# jtag-adapter-3-3.net
KiCad netlist of a schematic drawn in EAGLE
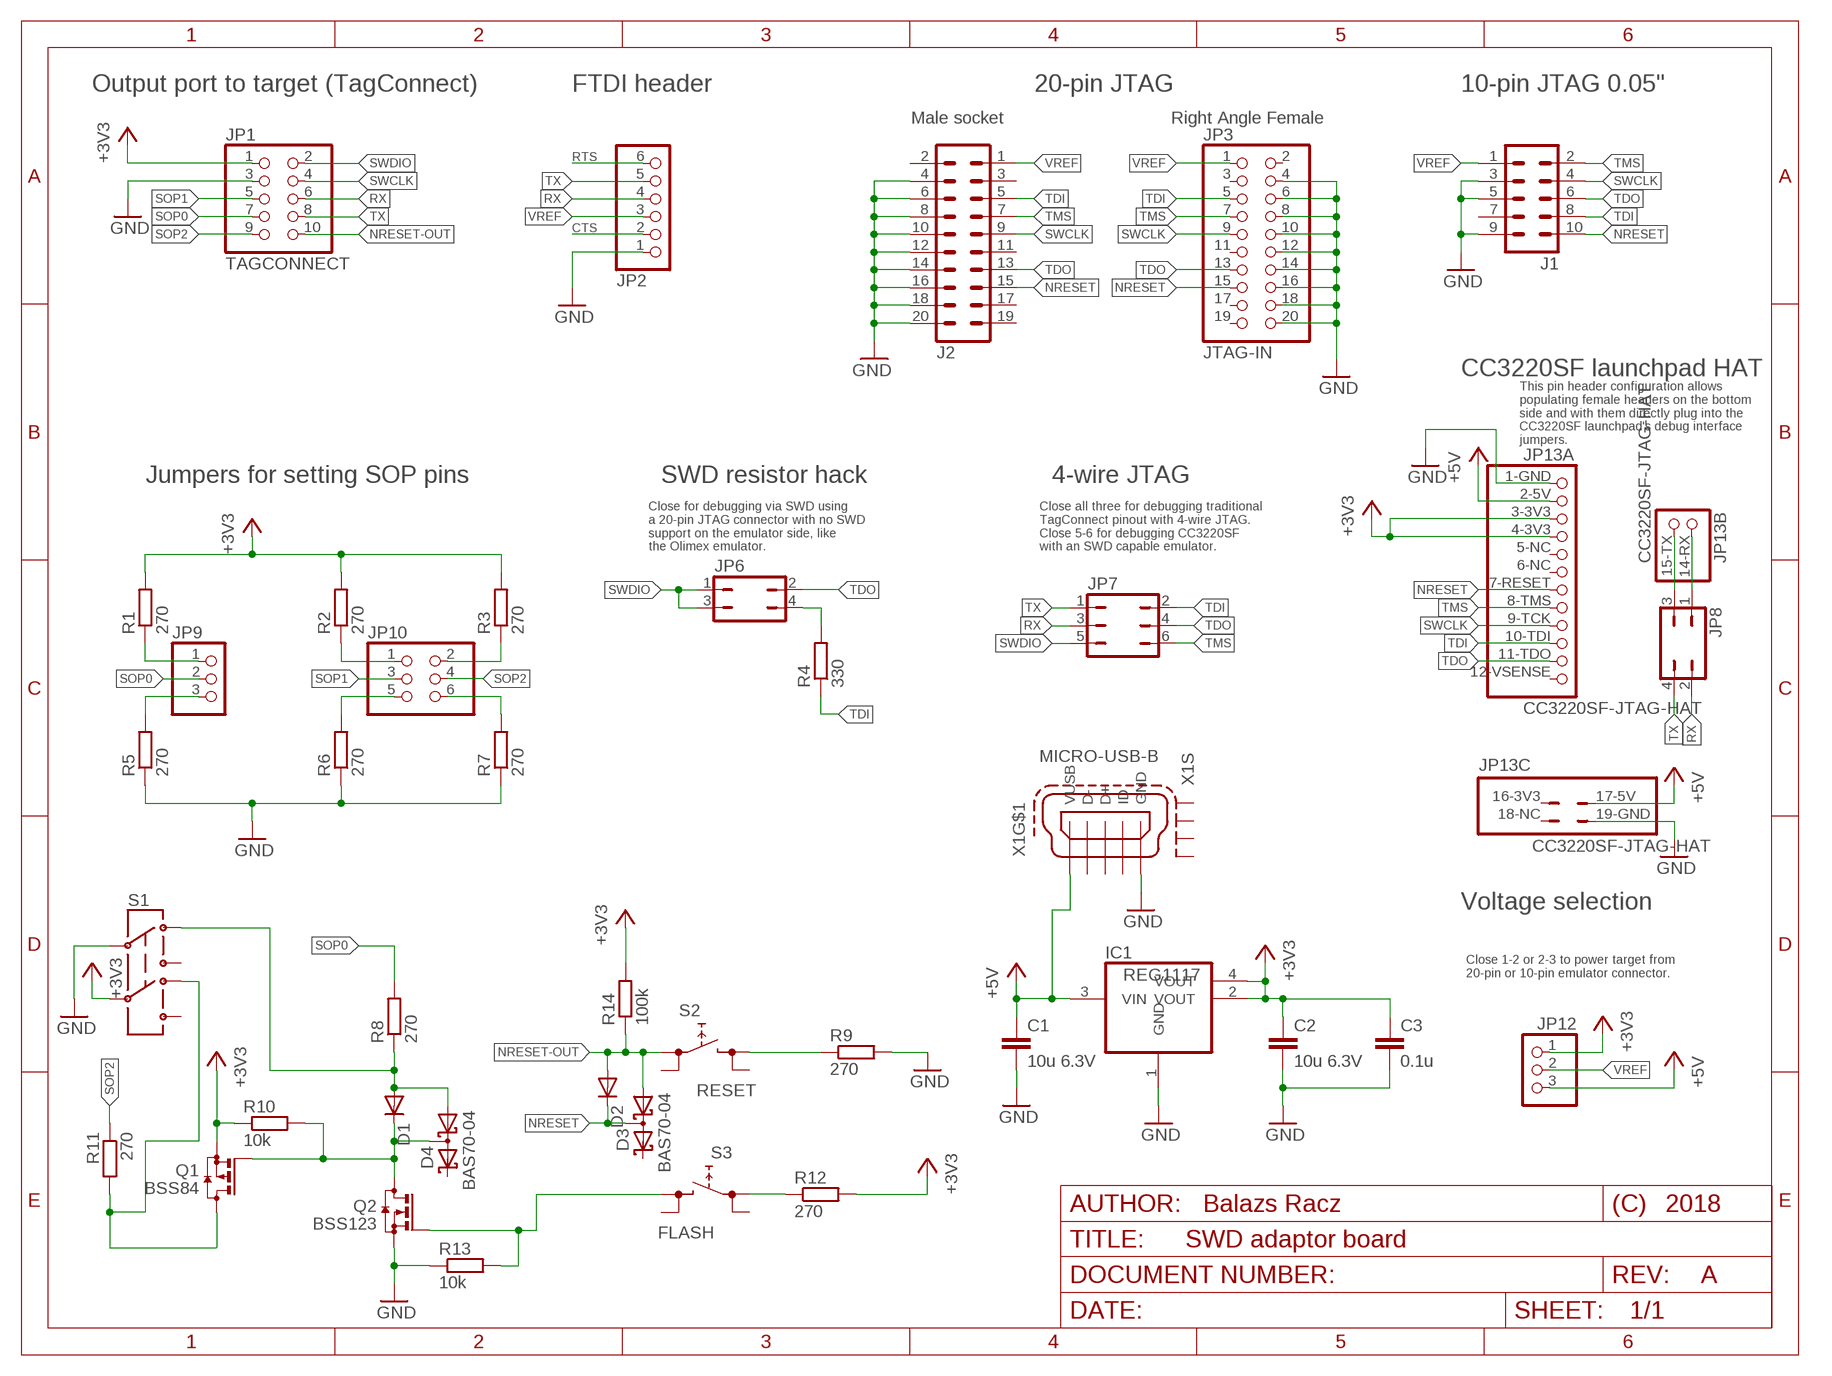
[diagram p0: schematic, sheet 1]

(export (version "E")
  (design (tool "Eeschema 10.0.6"))
  (components
    (comp (ref "C1")
      (value "10u 6.3V")
      (footprint "eagle-import:C0603K")
      (libsource (lib "eagle-import") (part "C-EUC0603K"))
    )
    (comp (ref "C2")
      (value "10u 6.3V")
      (footprint "eagle-import:C0603K")
      (libsource (lib "eagle-import") (part "C-EUC0603K"))
    )
    (comp (ref "C3")
      (value "0.1u")
      (footprint "eagle-import:C0603K")
      (libsource (lib "eagle-import") (part "C-EUC0603K"))
    )
    (comp (ref "D1")
      (value "DIODE-MINIMELF")
      (footprint "eagle-import:MINIMELF")
      (libsource (lib "eagle-import") (part "DIODE-MINIMELF"))
    )
    (comp (ref "D2")
      (value "DIODE-MINIMELF")
      (footprint "eagle-import:MINIMELF")
      (libsource (lib "eagle-import") (part "DIODE-MINIMELF"))
    )
    (comp (ref "D3")
      (value "BAS70-04")
      (footprint "eagle-import:SOT23")
      (libsource (lib "eagle-import") (part "BAS70-04"))
    )
    (comp (ref "D4")
      (value "BAS70-04")
      (footprint "eagle-import:SOT23")
      (libsource (lib "eagle-import") (part "BAS70-04"))
    )
    (comp (ref "IC1")
      (value "REG1117")
      (footprint "eagle-import:SOT223")
      (libsource (lib "eagle-import") (part "REG1117"))
    )
    (comp (ref "J1")
      (value "MA05-2_0.05X0.05")
      (footprint "eagle-import:MA05-2_0.05_X_0.05")
      (libsource (lib "eagle-import") (part "MA05-2_0.05X0.05"))
    )
    (comp (ref "J2")
      (value "MA10-2S")
      (footprint "eagle-import:MA10-2-SHROUDED")
      (libsource (lib "eagle-import") (part "MA10-2S"))
    )
    (comp (ref "JP1")
      (value "TAGCONNECT")
      (footprint "eagle-import:CON10M")
      (libsource (lib "eagle-import") (part "PINHD-2X5CN"))
    )
    (comp (ref "JP2")
      (value "PINHD-1X6")
      (footprint "eagle-import:1X06")
      (libsource (lib "eagle-import") (part "PINHD-1X6"))
    )
    (comp (ref "JP3")
      (value "JTAG-IN")
      (footprint "eagle-import:2X10")
      (libsource (lib "eagle-import") (part "PINHD-2X10"))
    )
    (comp (ref "JP6")
      (value "JP2Q")
      (footprint "eagle-import:JP2Q")
      (libsource (lib "eagle-import") (part "JP2Q"))
    )
    (comp (ref "JP7")
      (value "JP3Q")
      (footprint "eagle-import:JP3Q")
      (libsource (lib "eagle-import") (part "JP3Q"))
    )
    (comp (ref "JP8")
      (value "JP2Q")
      (footprint "eagle-import:JP2Q")
      (libsource (lib "eagle-import") (part "JP2Q"))
    )
    (comp (ref "JP9")
      (value "PINHD-1X3")
      (footprint "eagle-import:1X03")
      (libsource (lib "eagle-import") (part "PINHD-1X3"))
    )
    (comp (ref "JP10")
      (value "PINHD-2X3")
      (footprint "eagle-import:2X03")
      (libsource (lib "eagle-import") (part "PINHD-2X3"))
    )
    (comp (ref "JP12")
      (value "PINHD-1X3")
      (footprint "eagle-import:1X03")
      (libsource (lib "eagle-import") (part "PINHD-1X3"))
    )
    (comp (ref "JP13")
      (value "CC3220SF-JTAG-HAT")
      (footprint "eagle-import:JTAG-LAUNCHPAD-3220SF")
      (libsource (lib "eagle-import") (part "CC3220SF-JTAG-HAT"))
    )
    (comp (ref "Q1")
      (value "BSS84")
      (footprint "eagle-import:SOT23")
      (libsource (lib "eagle-import") (part "BSS84"))
    )
    (comp (ref "Q2")
      (value "BSS123")
      (footprint "eagle-import:SOT23")
      (libsource (lib "eagle-import") (part "BSS123"))
    )
    (comp (ref "R1")
      (value "270")
      (footprint "eagle-import:R0805")
      (libsource (lib "eagle-import") (part "R-EU_R0805"))
    )
    (comp (ref "R2")
      (value "270")
      (footprint "eagle-import:R0805")
      (libsource (lib "eagle-import") (part "R-EU_R0805"))
    )
    (comp (ref "R3")
      (value "270")
      (footprint "eagle-import:R0805")
      (libsource (lib "eagle-import") (part "R-EU_R0805"))
    )
    (comp (ref "R4")
      (value "330")
      (footprint "eagle-import:R0805")
      (libsource (lib "eagle-import") (part "R-EU_R0805"))
    )
    (comp (ref "R5")
      (value "270")
      (footprint "eagle-import:R0805")
      (libsource (lib "eagle-import") (part "R-EU_R0805"))
    )
    (comp (ref "R6")
      (value "270")
      (footprint "eagle-import:R0805")
      (libsource (lib "eagle-import") (part "R-EU_R0805"))
    )
    (comp (ref "R7")
      (value "270")
      (footprint "eagle-import:R0805")
      (libsource (lib "eagle-import") (part "R-EU_R0805"))
    )
    (comp (ref "R8")
      (value "270")
      (footprint "eagle-import:R0805")
      (libsource (lib "eagle-import") (part "R-EU_R0805"))
    )
    (comp (ref "R9")
      (value "270")
      (footprint "eagle-import:R0805")
      (libsource (lib "eagle-import") (part "R-EU_R0805"))
    )
    (comp (ref "R10")
      (value "10k")
      (footprint "eagle-import:R0805")
      (libsource (lib "eagle-import") (part "R-EU_R0805"))
    )
    (comp (ref "R11")
      (value "270")
      (footprint "eagle-import:R0805")
      (libsource (lib "eagle-import") (part "R-EU_R0805"))
    )
    (comp (ref "R12")
      (value "270")
      (footprint "eagle-import:R0805")
      (libsource (lib "eagle-import") (part "R-EU_R0805"))
    )
    (comp (ref "R13")
      (value "10k")
      (footprint "eagle-import:R0805")
      (libsource (lib "eagle-import") (part "R-EU_R0805"))
    )
    (comp (ref "R14")
      (value "100k")
      (footprint "eagle-import:R0805")
      (libsource (lib "eagle-import") (part "R-EU_R0805"))
    )
    (comp (ref "S1")
      (value "SWITCH-DPDTJS202011CQN")
      (footprint "eagle-import:DPDT-2.5X3.2MM")
      (libsource (lib "eagle-import") (part "SWITCH-DPDTJS202011CQN"))
    )
    (comp (ref "S2")
      (value "RESET")
      (footprint "eagle-import:TACTSW-6X6")
      (libsource (lib "eagle-import") (part "TACTSW-6X6S"))
    )
    (comp (ref "S3")
      (value "FLASH")
      (footprint "eagle-import:TACTSW-6X6")
      (libsource (lib "eagle-import") (part "TACTSW-6X6S"))
    )
    (comp (ref "X1")
      (value "MICRO-USB-B")
      (footprint "eagle-import:MICRO-B-PAC")
      (libsource (lib "eagle-import") (part "MICRO-USB-B"))
    )
  )
  (nets
    (net (code "1") (name "+3V3") (class "Default")
      (node (ref "C2") (pin "1") (pinfunction "1_1") (pintype "passive"))
      (node (ref "C3") (pin "1") (pinfunction "1_1") (pintype "passive"))
      (node (ref "IC1") (pin "2") (pinfunction "VOUT_2") (pintype "output"))
      (node (ref "IC1") (pin "4") (pinfunction "VOUT_4") (pintype "output"))
      (node (ref "JP1") (pin "1") (pinfunction "1_1") (pintype "passive"))
      (node (ref "JP12") (pin "1") (pinfunction "1_1") (pintype "passive"))
      (node (ref "JP13") (pin "3-3V3") (pinfunction "3_3-3V3") (pintype "passive"))
      (node (ref "JP13") (pin "4-3V3") (pinfunction "4_4-3V3") (pintype "passive"))
      (node (ref "Q1") (pin "2") (pinfunction "S_2") (pintype "passive"))
      (node (ref "R1") (pin "2") (pinfunction "2_2") (pintype "passive"))
      (node (ref "R10") (pin "1") (pinfunction "1_1") (pintype "passive"))
      (node (ref "R12") (pin "2") (pinfunction "2_2") (pintype "passive"))
      (node (ref "R14") (pin "2") (pinfunction "2_2") (pintype "passive"))
      (node (ref "R2") (pin "2") (pinfunction "2_2") (pintype "passive"))
      (node (ref "R3") (pin "2") (pinfunction "2_2") (pintype "passive"))
      (node (ref "S1") (pin "5") (pinfunction "2C_5") (pintype "bidirectional"))
    )
    (net (code "2") (name "+5V") (class "Default")
      (node (ref "C1") (pin "1") (pinfunction "1_1") (pintype "passive"))
      (node (ref "IC1") (pin "3") (pinfunction "VIN_3") (pintype "input"))
      (node (ref "JP12") (pin "3") (pinfunction "3_3") (pintype "passive"))
      (node (ref "JP13") (pin "17-5V") (pinfunction "2_17-5V") (pintype "passive"))
      (node (ref "JP13") (pin "2-5V") (pinfunction "2_2-5V") (pintype "passive"))
      (node (ref "X1") (pin "1") (pinfunction "VUSB_1") (pintype "passive"))
    )
    (net (code "3") (name "/CTS") (class "Default")
      (node (ref "JP2") (pin "2") (pinfunction "2_2") (pintype "passive"))
    )
    (net (code "4") (name "/RTS") (class "Default")
      (node (ref "JP2") (pin "6") (pinfunction "6_6") (pintype "passive"))
    )
    (net (code "5") (name "GND") (class "Default")
      (node (ref "C1") (pin "2") (pinfunction "2_2") (pintype "passive"))
      (node (ref "C2") (pin "2") (pinfunction "2_2") (pintype "passive"))
      (node (ref "C3") (pin "2") (pinfunction "2_2") (pintype "passive"))
      (node (ref "IC1") (pin "1") (pinfunction "GND_1") (pintype "power_in"))
      (node (ref "J1") (pin "3") (pinfunction "3_3") (pintype "passive"))
      (node (ref "J1") (pin "5") (pinfunction "5_5") (pintype "passive"))
      (node (ref "J1") (pin "9") (pinfunction "9_9") (pintype "passive"))
      (node (ref "J2") (pin "10") (pinfunction "10_10") (pintype "passive"))
      (node (ref "J2") (pin "12") (pinfunction "12_12") (pintype "passive"))
      (node (ref "J2") (pin "14") (pinfunction "14_14") (pintype "passive"))
      (node (ref "J2") (pin "16") (pinfunction "16_16") (pintype "passive"))
      (node (ref "J2") (pin "18") (pinfunction "18_18") (pintype "passive"))
      (node (ref "J2") (pin "20") (pinfunction "20_20") (pintype "passive"))
      (node (ref "J2") (pin "4") (pinfunction "4_4") (pintype "passive"))
      (node (ref "J2") (pin "6") (pinfunction "6_6") (pintype "passive"))
      (node (ref "J2") (pin "8") (pinfunction "8_8") (pintype "passive"))
      (node (ref "JP1") (pin "3") (pinfunction "3_3") (pintype "passive"))
      (node (ref "JP13") (pin "1-GND") (pinfunction "1_1-GND") (pintype "passive"))
      (node (ref "JP13") (pin "19-GND") (pinfunction "4_19-GND") (pintype "passive"))
      (node (ref "JP2") (pin "1") (pinfunction "1_1") (pintype "passive"))
      (node (ref "JP3") (pin "10") (pinfunction "10_10") (pintype "passive"))
      (node (ref "JP3") (pin "12") (pinfunction "12_12") (pintype "passive"))
      (node (ref "JP3") (pin "14") (pinfunction "14_14") (pintype "passive"))
      (node (ref "JP3") (pin "16") (pinfunction "16_16") (pintype "passive"))
      (node (ref "JP3") (pin "18") (pinfunction "18_18") (pintype "passive"))
      (node (ref "JP3") (pin "20") (pinfunction "20_20") (pintype "passive"))
      (node (ref "JP3") (pin "4") (pinfunction "4_4") (pintype "passive"))
      (node (ref "JP3") (pin "6") (pinfunction "6_6") (pintype "passive"))
      (node (ref "JP3") (pin "8") (pinfunction "8_8") (pintype "passive"))
      (node (ref "Q2") (pin "2") (pinfunction "S_2") (pintype "passive"))
      (node (ref "R13") (pin "1") (pinfunction "1_1") (pintype "passive"))
      (node (ref "R5") (pin "1") (pinfunction "1_1") (pintype "passive"))
      (node (ref "R6") (pin "1") (pinfunction "1_1") (pintype "passive"))
      (node (ref "R7") (pin "1") (pinfunction "1_1") (pintype "passive"))
      (node (ref "R9") (pin "2") (pinfunction "2_2") (pintype "passive"))
      (node (ref "S1") (pin "2") (pinfunction "1C_2") (pintype "bidirectional"))
      (node (ref "X1") (pin "5") (pinfunction "GND_5") (pintype "passive"))
    )
    (net (code "6") (name "NRESET") (class "Default")
      (node (ref "D2") (pin "C") (pinfunction "C_C") (pintype "passive"))
      (node (ref "D3") (pin "3") (pinfunction "C1A2_3") (pintype "passive"))
      (node (ref "J1") (pin "10") (pinfunction "10_10") (pintype "passive"))
      (node (ref "J2") (pin "15") (pinfunction "15_15") (pintype "passive"))
      (node (ref "JP13") (pin "7-RESET") (pinfunction "7_7-RESET") (pintype "passive"))
      (node (ref "JP3") (pin "15") (pinfunction "15_15") (pintype "passive"))
    )
    (net (code "7") (name "NRESET-OUT") (class "Default")
      (node (ref "D2") (pin "A") (pinfunction "A_A") (pintype "passive"))
      (node (ref "D3") (pin "1") (pinfunction "A1_1") (pintype "passive"))
      (node (ref "JP1") (pin "10") (pinfunction "10_10") (pintype "passive"))
      (node (ref "R14") (pin "1") (pinfunction "1_1") (pintype "passive"))
      (node (ref "S2") (pin "1") (pinfunction "1.1_1") (pintype "passive"))
    )
    (net (code "8") (name "Net-(D4-A1)") (class "Default")
      (node (ref "D1") (pin "A") (pinfunction "A_A") (pintype "passive"))
      (node (ref "D4") (pin "1") (pinfunction "A1_1") (pintype "passive"))
      (node (ref "R8") (pin "1") (pinfunction "1_1") (pintype "passive"))
      (node (ref "S1") (pin "1") (pinfunction "1A_1") (pintype "bidirectional"))
    )
    (net (code "9") (name "Net-(D4-C1A2)") (class "Default")
      (node (ref "D1") (pin "C") (pinfunction "C_C") (pintype "passive"))
      (node (ref "D4") (pin "3") (pinfunction "C1A2_3") (pintype "passive"))
      (node (ref "Q1") (pin "1") (pinfunction "G_1") (pintype "passive"))
      (node (ref "Q2") (pin "3") (pinfunction "D_3") (pintype "passive"))
      (node (ref "R10") (pin "2") (pinfunction "2_2") (pintype "passive"))
    )
    (net (code "10") (name "Net-(JP6-Pad4)") (class "Default")
      (node (ref "JP6") (pin "4") (pinfunction "4_4") (pintype "passive"))
      (node (ref "R4") (pin "2") (pinfunction "2_2") (pintype "passive"))
    )
    (net (code "11") (name "Net-(JP9-Pad1)") (class "Default")
      (node (ref "JP9") (pin "1") (pinfunction "1_1") (pintype "passive"))
      (node (ref "R1") (pin "1") (pinfunction "1_1") (pintype "passive"))
    )
    (net (code "12") (name "Net-(JP9-Pad3)") (class "Default")
      (node (ref "JP9") (pin "3") (pinfunction "3_3") (pintype "passive"))
      (node (ref "R5") (pin "2") (pinfunction "2_2") (pintype "passive"))
    )
    (net (code "13") (name "Net-(JP10-Pad1)") (class "Default")
      (node (ref "JP10") (pin "1") (pinfunction "1_1") (pintype "passive"))
      (node (ref "R2") (pin "1") (pinfunction "1_1") (pintype "passive"))
    )
    (net (code "14") (name "Net-(JP10-Pad2)") (class "Default")
      (node (ref "JP10") (pin "2") (pinfunction "2_2") (pintype "passive"))
      (node (ref "R3") (pin "1") (pinfunction "1_1") (pintype "passive"))
    )
    (net (code "15") (name "Net-(JP10-Pad5)") (class "Default")
      (node (ref "JP10") (pin "5") (pinfunction "5_5") (pintype "passive"))
      (node (ref "R6") (pin "2") (pinfunction "2_2") (pintype "passive"))
    )
    (net (code "16") (name "Net-(JP10-Pad6)") (class "Default")
      (node (ref "JP10") (pin "6") (pinfunction "6_6") (pintype "passive"))
      (node (ref "R7") (pin "2") (pinfunction "2_2") (pintype "passive"))
    )
    (net (code "17") (name "Net-(JP13B-1)") (class "Default")
      (node (ref "JP13") (pin "14-RX") (pinfunction "1_14-RX") (pintype "passive"))
      (node (ref "JP8") (pin "1") (pinfunction "1_1") (pintype "passive"))
    )
    (net (code "18") (name "Net-(JP13B-2)") (class "Default")
      (node (ref "JP13") (pin "15-TX") (pinfunction "2_15-TX") (pintype "passive"))
      (node (ref "JP8") (pin "3") (pinfunction "3_3") (pintype "passive"))
    )
    (net (code "19") (name "Net-(Q1-D)") (class "Default")
      (node (ref "Q1") (pin "3") (pinfunction "D_3") (pintype "passive"))
      (node (ref "R11") (pin "2") (pinfunction "2_2") (pintype "passive"))
      (node (ref "S1") (pin "4") (pinfunction "2A_4") (pintype "bidirectional"))
    )
    (net (code "20") (name "Net-(Q2-G)") (class "Default")
      (node (ref "Q2") (pin "1") (pinfunction "G_1") (pintype "passive"))
      (node (ref "R13") (pin "2") (pinfunction "2_2") (pintype "passive"))
      (node (ref "S3") (pin "3") (pinfunction "2.1_3") (pintype "passive"))
    )
    (net (code "21") (name "Net-(S2-2.1)") (class "Default")
      (node (ref "R9") (pin "1") (pinfunction "1_1") (pintype "passive"))
      (node (ref "S2") (pin "3") (pinfunction "2.1_3") (pintype "passive"))
    )
    (net (code "22") (name "Net-(S3-1.1)") (class "Default")
      (node (ref "R12") (pin "1") (pinfunction "1_1") (pintype "passive"))
      (node (ref "S3") (pin "1") (pinfunction "1.1_1") (pintype "passive"))
    )
    (net (code "23") (name "RX") (class "Default")
      (node (ref "JP1") (pin "6") (pinfunction "6_6") (pintype "passive"))
      (node (ref "JP2") (pin "4") (pinfunction "4_4") (pintype "passive"))
      (node (ref "JP7") (pin "3") (pinfunction "3_3") (pintype "passive"))
      (node (ref "JP8") (pin "2") (pinfunction "2_2") (pintype "passive"))
    )
    (net (code "24") (name "SOP0") (class "Default")
      (node (ref "JP1") (pin "7") (pinfunction "7_7") (pintype "passive"))
      (node (ref "JP9") (pin "2") (pinfunction "2_2") (pintype "passive"))
      (node (ref "R8") (pin "2") (pinfunction "2_2") (pintype "passive"))
    )
    (net (code "25") (name "SOP1") (class "Default")
      (node (ref "JP1") (pin "5") (pinfunction "5_5") (pintype "passive"))
      (node (ref "JP10") (pin "3") (pinfunction "3_3") (pintype "passive"))
    )
    (net (code "26") (name "SOP2") (class "Default")
      (node (ref "JP1") (pin "9") (pinfunction "9_9") (pintype "passive"))
      (node (ref "JP10") (pin "4") (pinfunction "4_4") (pintype "passive"))
      (node (ref "R11") (pin "1") (pinfunction "1_1") (pintype "passive"))
    )
    (net (code "27") (name "SWCLK") (class "Default")
      (node (ref "J1") (pin "4") (pinfunction "4_4") (pintype "passive"))
      (node (ref "J2") (pin "9") (pinfunction "9_9") (pintype "passive"))
      (node (ref "JP1") (pin "4") (pinfunction "4_4") (pintype "passive"))
      (node (ref "JP13") (pin "9-TCK") (pinfunction "9_9-TCK") (pintype "passive"))
      (node (ref "JP3") (pin "9") (pinfunction "9_9") (pintype "passive"))
    )
    (net (code "28") (name "SWDIO") (class "Default")
      (node (ref "JP1") (pin "2") (pinfunction "2_2") (pintype "passive"))
      (node (ref "JP6") (pin "1") (pinfunction "1_1") (pintype "passive"))
      (node (ref "JP6") (pin "3") (pinfunction "3_3") (pintype "passive"))
      (node (ref "JP7") (pin "5") (pinfunction "5_5") (pintype "passive"))
    )
    (net (code "29") (name "TDI") (class "Default")
      (node (ref "J1") (pin "8") (pinfunction "8_8") (pintype "passive"))
      (node (ref "J2") (pin "5") (pinfunction "5_5") (pintype "passive"))
      (node (ref "JP13") (pin "10-TDI") (pinfunction "10_10-TDI") (pintype "passive"))
      (node (ref "JP3") (pin "5") (pinfunction "5_5") (pintype "passive"))
      (node (ref "JP7") (pin "2") (pinfunction "2_2") (pintype "passive"))
      (node (ref "R4") (pin "1") (pinfunction "1_1") (pintype "passive"))
    )
    (net (code "30") (name "TDO") (class "Default")
      (node (ref "J1") (pin "6") (pinfunction "6_6") (pintype "passive"))
      (node (ref "J2") (pin "13") (pinfunction "13_13") (pintype "passive"))
      (node (ref "JP13") (pin "11-TDO") (pinfunction "11_11-TDO") (pintype "passive"))
      (node (ref "JP3") (pin "13") (pinfunction "13_13") (pintype "passive"))
      (node (ref "JP6") (pin "2") (pinfunction "2_2") (pintype "passive"))
      (node (ref "JP7") (pin "4") (pinfunction "4_4") (pintype "passive"))
    )
    (net (code "31") (name "TMS") (class "Default")
      (node (ref "J1") (pin "2") (pinfunction "2_2") (pintype "passive"))
      (node (ref "J2") (pin "7") (pinfunction "7_7") (pintype "passive"))
      (node (ref "JP13") (pin "8-TMS") (pinfunction "8_8-TMS") (pintype "passive"))
      (node (ref "JP3") (pin "7") (pinfunction "7_7") (pintype "passive"))
      (node (ref "JP7") (pin "6") (pinfunction "6_6") (pintype "passive"))
    )
    (net (code "32") (name "TX") (class "Default")
      (node (ref "JP1") (pin "8") (pinfunction "8_8") (pintype "passive"))
      (node (ref "JP2") (pin "5") (pinfunction "5_5") (pintype "passive"))
      (node (ref "JP7") (pin "1") (pinfunction "1_1") (pintype "passive"))
      (node (ref "JP8") (pin "4") (pinfunction "4_4") (pintype "passive"))
    )
    (net (code "33") (name "VREF") (class "Default")
      (node (ref "J1") (pin "1") (pinfunction "1_1") (pintype "passive"))
      (node (ref "J2") (pin "1") (pinfunction "1_1") (pintype "passive"))
      (node (ref "JP12") (pin "2") (pinfunction "2_2") (pintype "passive"))
      (node (ref "JP2") (pin "3") (pinfunction "3_3") (pintype "passive"))
      (node (ref "JP3") (pin "1") (pinfunction "1_1") (pintype "passive"))
    )
    (net (code "34") (name "unconnected-(D3-C2-Pad2)") (class "Default")
      (node (ref "D3") (pin "2") (pinfunction "C2_2") (pintype "passive"))
    )
    (net (code "35") (name "unconnected-(D4-C2-Pad2)") (class "Default")
      (node (ref "D4") (pin "2") (pinfunction "C2_2") (pintype "passive"))
    )
    (net (code "36") (name "unconnected-(J1-Pad7)") (class "Default")
      (node (ref "J1") (pin "7") (pinfunction "7_7") (pintype "passive"))
    )
    (net (code "37") (name "unconnected-(J2-Pad2)") (class "Default")
      (node (ref "J2") (pin "2") (pinfunction "2_2") (pintype "passive"))
    )
    (net (code "38") (name "unconnected-(J2-Pad3)") (class "Default")
      (node (ref "J2") (pin "3") (pinfunction "3_3") (pintype "passive"))
    )
    (net (code "39") (name "unconnected-(J2-Pad11)") (class "Default")
      (node (ref "J2") (pin "11") (pinfunction "11_11") (pintype "passive"))
    )
    (net (code "40") (name "unconnected-(J2-Pad17)") (class "Default")
      (node (ref "J2") (pin "17") (pinfunction "17_17") (pintype "passive"))
    )
    (net (code "41") (name "unconnected-(J2-Pad19)") (class "Default")
      (node (ref "J2") (pin "19") (pinfunction "19_19") (pintype "passive"))
    )
    (net (code "42") (name "unconnected-(JP3-Pad2)") (class "Default")
      (node (ref "JP3") (pin "2") (pinfunction "2_2") (pintype "passive"))
    )
    (net (code "43") (name "unconnected-(JP3-Pad3)") (class "Default")
      (node (ref "JP3") (pin "3") (pinfunction "3_3") (pintype "passive"))
    )
    (net (code "44") (name "unconnected-(JP3-Pad11)") (class "Default")
      (node (ref "JP3") (pin "11") (pinfunction "11_11") (pintype "passive"))
    )
    (net (code "45") (name "unconnected-(JP3-Pad17)") (class "Default")
      (node (ref "JP3") (pin "17") (pinfunction "17_17") (pintype "passive"))
    )
    (net (code "46") (name "unconnected-(JP3-Pad19)") (class "Default")
      (node (ref "JP3") (pin "19") (pinfunction "19_19") (pintype "passive"))
    )
    (net (code "47") (name "unconnected-(JP13A-5-Pad5-NC)") (class "Default")
      (node (ref "JP13") (pin "5-NC") (pinfunction "5_5-NC") (pintype "passive"))
    )
    (net (code "48") (name "unconnected-(JP13A-6-Pad6-NC)") (class "Default")
      (node (ref "JP13") (pin "6-NC") (pinfunction "6_6-NC") (pintype "passive"))
    )
    (net (code "49") (name "unconnected-(JP13A-12-Pad12-VSENSE)") (class "Default")
      (node (ref "JP13") (pin "12-VSENSE") (pinfunction "12_12-VSENSE") (pintype "passive"))
    )
    (net (code "50") (name "unconnected-(JP13C-1-Pad16-3V3)") (class "Default")
      (node (ref "JP13") (pin "16-3V3") (pinfunction "1_16-3V3") (pintype "passive"))
    )
    (net (code "51") (name "unconnected-(JP13C-3-Pad18-NC)") (class "Default")
      (node (ref "JP13") (pin "18-NC") (pinfunction "3_18-NC") (pintype "passive"))
    )
    (net (code "52") (name "unconnected-(S1-1B-Pad3)") (class "Default")
      (node (ref "S1") (pin "3") (pinfunction "1B_3") (pintype "bidirectional"))
    )
    (net (code "53") (name "unconnected-(S1-2B-Pad6)") (class "Default")
      (node (ref "S1") (pin "6") (pinfunction "2B_6") (pintype "bidirectional"))
    )
    (net (code "54") (name "unconnected-(S2-1.2-Pad2)") (class "Default")
      (node (ref "S2") (pin "2") (pinfunction "1.2_2") (pintype "passive"))
    )
    (net (code "55") (name "unconnected-(S2-2.2-Pad4)") (class "Default")
      (node (ref "S2") (pin "4") (pinfunction "2.2_4") (pintype "passive"))
    )
    (net (code "56") (name "unconnected-(S3-1.2-Pad2)") (class "Default")
      (node (ref "S3") (pin "2") (pinfunction "1.2_2") (pintype "passive"))
    )
    (net (code "57") (name "unconnected-(S3-2.2-Pad4)") (class "Default")
      (node (ref "S3") (pin "4") (pinfunction "2.2_4") (pintype "passive"))
    )
    (net (code "58") (name "unconnected-(X1A-D+-Pad3)") (class "Default")
      (node (ref "X1") (pin "3") (pinfunction "D+_3") (pintype "passive"))
    )
    (net (code "59") (name "unconnected-(X1A-D--Pad2)") (class "Default")
      (node (ref "X1") (pin "2") (pinfunction "D-_2") (pintype "passive"))
    )
    (net (code "60") (name "unconnected-(X1A-ID-Pad4)") (class "Default")
      (node (ref "X1") (pin "4") (pinfunction "ID_4") (pintype "passive"))
    )
    (net (code "61") (name "unconnected-(X1B-S1-PadM1)") (class "Default")
      (node (ref "X1") (pin "M1") (pinfunction "S1_M1") (pintype "passive"))
    )
    (net (code "62") (name "unconnected-(X1B-S2-PadM2)") (class "Default")
      (node (ref "X1") (pin "M2") (pinfunction "S2_M2") (pintype "passive"))
    )
    (net (code "63") (name "unconnected-(X1B-S3-PadM3)") (class "Default")
      (node (ref "X1") (pin "M3") (pinfunction "S3_M3") (pintype "passive"))
    )
    (net (code "64") (name "unconnected-(X1B-S4-PadM4)") (class "Default")
      (node (ref "X1") (pin "M4") (pinfunction "S4_M4") (pintype "passive"))
    )
  )
)
